# dtmf_v1.net
KiCad netlist of a schematic drawn in EAGLE
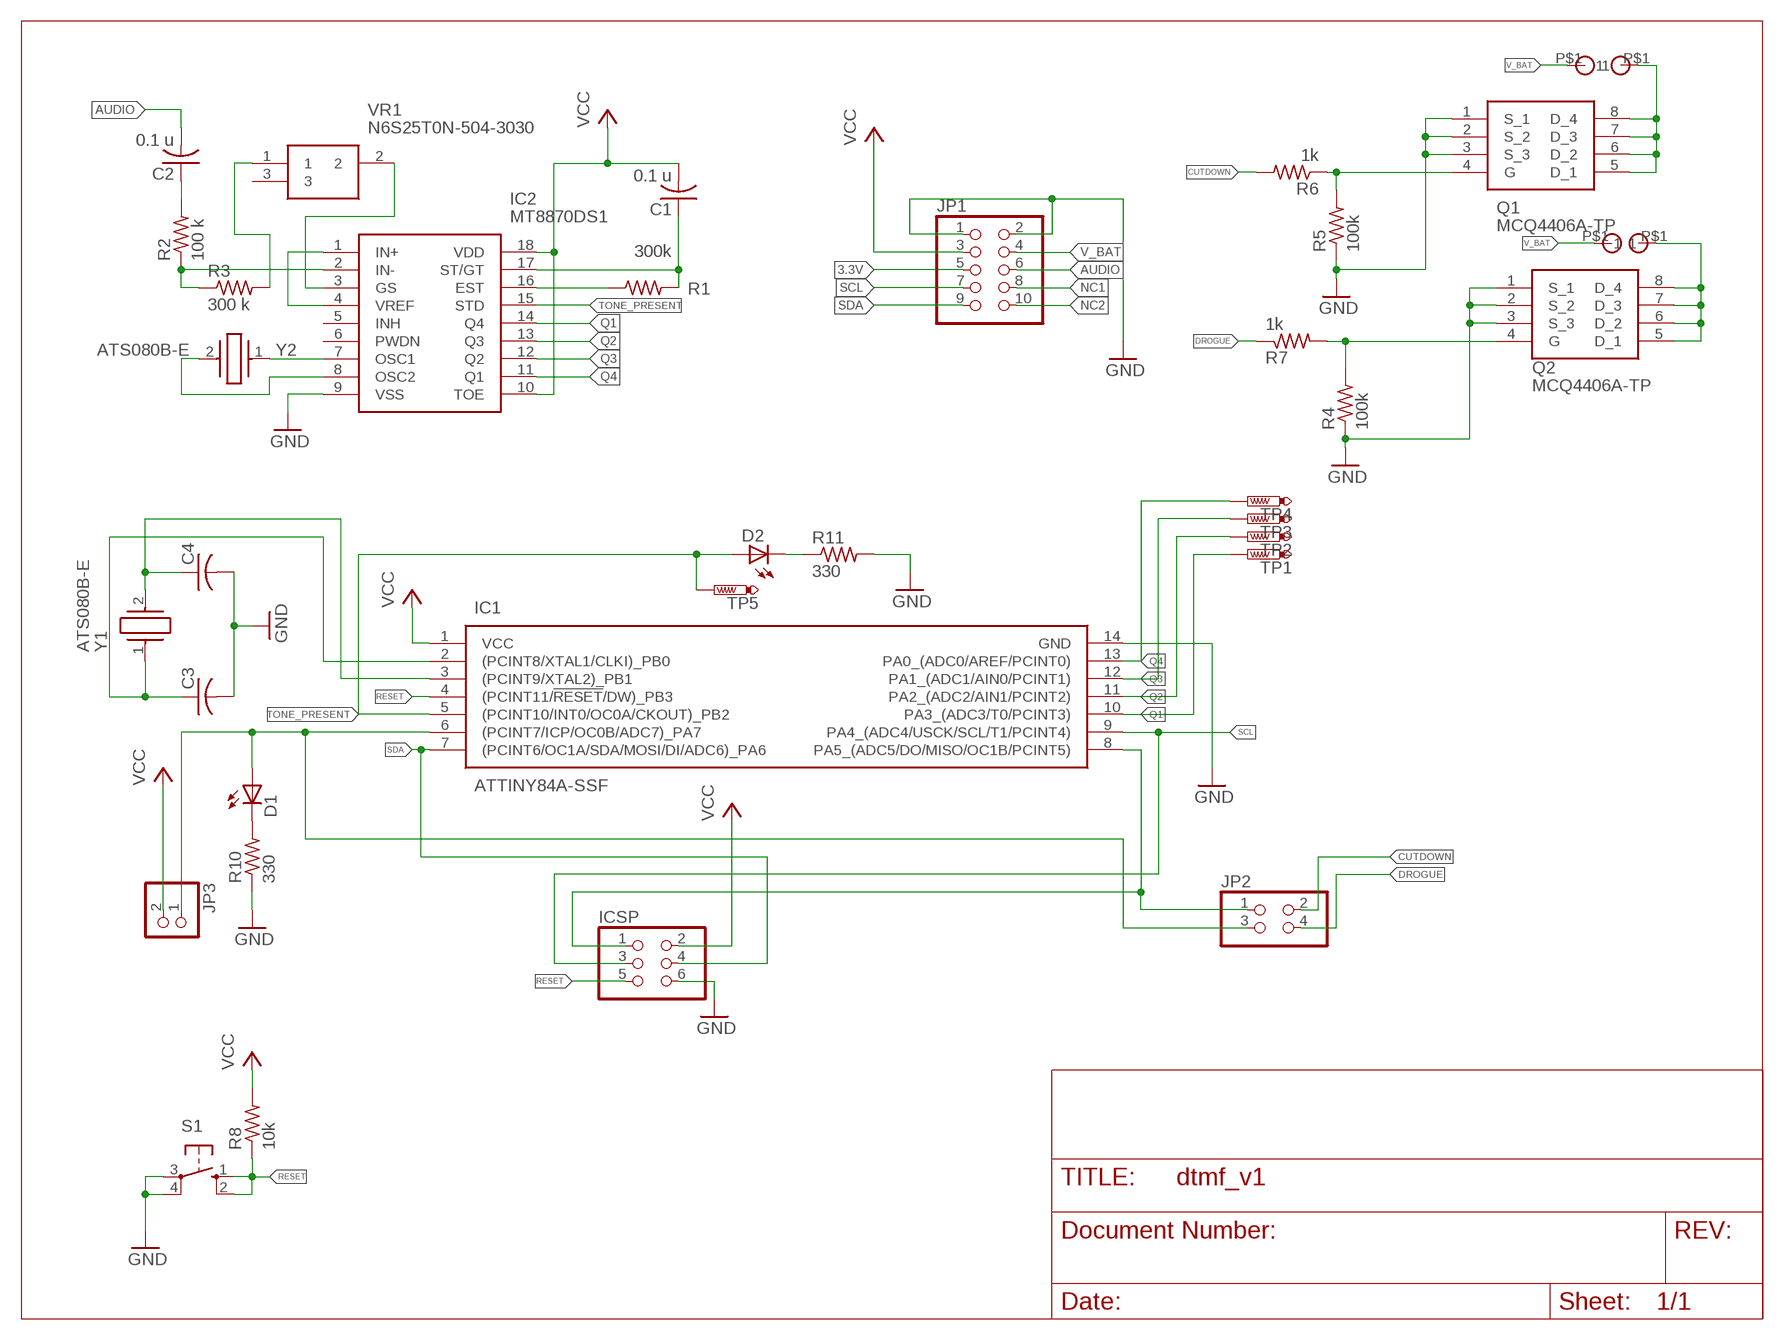
[diagram p0: schematic, sheet 1]

(export (version "E")
  (design (tool "Eeschema 10.0.6"))
  (components
    (comp (ref "C1")
      (value "0.1 u")
      (footprint "eagle-import:C0603")
      (libsource (lib "eagle-import") (part "C-USC0603"))
    )
    (comp (ref "C2")
      (value "0.1 u")
      (footprint "eagle-import:C0603")
      (libsource (lib "eagle-import") (part "C-USC0603"))
    )
    (comp (ref "C3")
      (value "C-USC0805")
      (footprint "eagle-import:C0805")
      (libsource (lib "eagle-import") (part "C-USC0805"))
    )
    (comp (ref "C4")
      (value "C-USC0805")
      (footprint "eagle-import:C0805")
      (libsource (lib "eagle-import") (part "C-USC0805"))
    )
    (comp (ref "D1")
      (value "LEDCHIP-LED0805")
      (footprint "eagle-import:CHIP-LED0805")
      (libsource (lib "eagle-import") (part "LEDCHIP-LED0805"))
    )
    (comp (ref "D2")
      (value "LEDCHIP-LED0805")
      (footprint "eagle-import:CHIP-LED0805")
      (libsource (lib "eagle-import") (part "LEDCHIP-LED0805"))
    )
    (comp (ref "IC1")
      (value "ATTINY84A-SSF")
      (footprint "eagle-import:SOIC127P600X175-14N")
      (fields (field (name "MOUSER_PART_NUMBER") "556-ATTINY84A-SSF"))
      (libsource (lib "eagle-import") (part "ATTINY84A-SSF"))
    )
    (comp (ref "IC2")
      (value "MT8870DS1")
      (footprint "eagle-import:SOIC127P1032X265-18N")
      (fields (field (name "MOUSER_PART_NUMBER") "494-MT8870DS1"))
      (libsource (lib "eagle-import") (part "MT8870DS1"))
    )
    (comp (ref "ICSP")
      (value "PINHD-2X3")
      (footprint "eagle-import:2X03")
      (libsource (lib "eagle-import") (part "PINHD-2X3"))
    )
    (comp (ref "JP1")
      (value "PINHD-2X5")
      (footprint "eagle-import:2X05")
      (libsource (lib "eagle-import") (part "PINHD-2X5"))
    )
    (comp (ref "JP2")
      (value "PINHD-2X2")
      (footprint "eagle-import:2X02")
      (libsource (lib "eagle-import") (part "PINHD-2X2"))
    )
    (comp (ref "JP3")
      (value "PINHD-1X2")
      (footprint "eagle-import:1X02")
      (libsource (lib "eagle-import") (part "PINHD-1X2"))
    )
    (comp (ref "Q1")
      (value "MCQ4406A-TP")
      (footprint "eagle-import:SOIC127P600X175-8N")
      (fields (field (name "MOUSER_PART_NUMBER") "833-MCQ4406A-TP"))
      (libsource (lib "eagle-import") (part "MCQ4406A-TP"))
    )
    (comp (ref "Q2")
      (value "MCQ4406A-TP")
      (footprint "eagle-import:SOIC127P600X175-8N")
      (fields (field (name "MOUSER_PART_NUMBER") "833-MCQ4406A-TP"))
      (libsource (lib "eagle-import") (part "MCQ4406A-TP"))
    )
    (comp (ref "R1")
      (value "300k")
      (footprint "eagle-import:M0805")
      (libsource (lib "eagle-import") (part "R-US_M0805"))
    )
    (comp (ref "R2")
      (value "100 k")
      (footprint "eagle-import:M0805")
      (libsource (lib "eagle-import") (part "R-US_M0805"))
    )
    (comp (ref "R3")
      (value "300 k")
      (footprint "eagle-import:M0805")
      (libsource (lib "eagle-import") (part "R-US_M0805"))
    )
    (comp (ref "R4")
      (value "100k")
      (footprint "eagle-import:M0805")
      (libsource (lib "eagle-import") (part "R-US_M0805"))
    )
    (comp (ref "R5")
      (value "100k")
      (footprint "eagle-import:M0805")
      (libsource (lib "eagle-import") (part "R-US_M0805"))
    )
    (comp (ref "R6")
      (value "1k")
      (footprint "eagle-import:M0805")
      (libsource (lib "eagle-import") (part "R-US_M0805"))
    )
    (comp (ref "R7")
      (value "1k")
      (footprint "eagle-import:M0805")
      (libsource (lib "eagle-import") (part "R-US_M0805"))
    )
    (comp (ref "R8")
      (value "10k")
      (footprint "eagle-import:0207_10")
      (libsource (lib "eagle-import") (part "R-US_0207/10"))
    )
    (comp (ref "R10")
      (value "330")
      (footprint "eagle-import:M0805")
      (libsource (lib "eagle-import") (part "R-US_M0805"))
    )
    (comp (ref "R11")
      (value "330")
      (footprint "eagle-import:M0805")
      (libsource (lib "eagle-import") (part "R-US_M0805"))
    )
    (comp (ref "S1")
      (value "10-XX")
      (footprint "eagle-import:B3F-10XX")
      (fields (field (name "MPN") "B3F-1000"))
      (libsource (lib "eagle-import") (part "10-XX"))
    )
    (comp (ref "TP1")
      (value "PTR1B1,27")
      (footprint "eagle-import:B1,27")
      (libsource (lib "eagle-import") (part "PTR1B1,27"))
    )
    (comp (ref "TP2")
      (value "PTR1B1,27")
      (footprint "eagle-import:B1,27")
      (libsource (lib "eagle-import") (part "PTR1B1,27"))
    )
    (comp (ref "TP3")
      (value "PTR1B1,27")
      (footprint "eagle-import:B1,27")
      (libsource (lib "eagle-import") (part "PTR1B1,27"))
    )
    (comp (ref "TP4")
      (value "PTR1B1,27")
      (footprint "eagle-import:B1,27")
      (libsource (lib "eagle-import") (part "PTR1B1,27"))
    )
    (comp (ref "TP5")
      (value "PTR1B1,27")
      (footprint "eagle-import:B1,27")
      (libsource (lib "eagle-import") (part "PTR1B1,27"))
    )
    (comp (ref "U$1")
      (value "M3_HOLE")
      (footprint "eagle-import:MOUNTING_PAD")
      (libsource (lib "eagle-import") (part "M3_HOLE"))
    )
    (comp (ref "U$2")
      (value "M3_HOLE")
      (footprint "eagle-import:MOUNTING_PAD")
      (libsource (lib "eagle-import") (part "M3_HOLE"))
    )
    (comp (ref "U$3")
      (value "M3_HOLE")
      (footprint "eagle-import:MOUNTING_PAD")
      (libsource (lib "eagle-import") (part "M3_HOLE"))
    )
    (comp (ref "U$4")
      (value "M3_HOLE")
      (footprint "eagle-import:MOUNTING_PAD")
      (libsource (lib "eagle-import") (part "M3_HOLE"))
    )
    (comp (ref "VR1")
      (value "N6S25T0N-504-3030")
      (footprint "eagle-import:N6S25T0N5043030")
      (fields (field (name "MOUSER_PART_NUMBER") "531-N6S25T0N5043030"))
      (libsource (lib "eagle-import") (part "N6S25T0N-504-3030"))
    )
    (comp (ref "Y1")
      (value "ATS080B-E")
      (footprint "eagle-import:ATS080BE")
      (fields (field (name "MOUSER_PART_NUMBER") "774-ATS080B-E"))
      (libsource (lib "eagle-import") (part "ATS080B-E"))
    )
    (comp (ref "Y2")
      (value "ATS080B-E")
      (footprint "eagle-import:ATS080BE")
      (fields (field (name "MOUSER_PART_NUMBER") "774-ATS080B-E"))
      (libsource (lib "eagle-import") (part "ATS080B-E"))
    )
  )
  (nets
    (net (code "1") (name "3.3V") (class "Default")
      (node (ref "JP1") (pin "5") (pinfunction "5_5") (pintype "passive"))
    )
    (net (code "2") (name "AUDIO") (class "Default")
      (node (ref "C2") (pin "2") (pinfunction "2_2") (pintype "passive"))
      (node (ref "JP1") (pin "6") (pinfunction "6_6") (pintype "passive"))
    )
    (net (code "3") (name "CUTDOWN") (class "Default")
      (node (ref "JP2") (pin "2") (pinfunction "2_2") (pintype "passive"))
      (node (ref "R6") (pin "2") (pinfunction "2_2") (pintype "passive"))
    )
    (net (code "4") (name "DROGUE") (class "Default")
      (node (ref "JP2") (pin "4") (pinfunction "4_4") (pintype "passive"))
      (node (ref "R7") (pin "1") (pinfunction "1_1") (pintype "passive"))
    )
    (net (code "5") (name "GND") (class "Default")
      (node (ref "C3") (pin "2") (pinfunction "2_2") (pintype "passive"))
      (node (ref "C4") (pin "2") (pinfunction "2_2") (pintype "passive"))
      (node (ref "IC1") (pin "14") (pinfunction "GND_14") (pintype "bidirectional"))
      (node (ref "IC2") (pin "9") (pinfunction "VSS_9") (pintype "bidirectional"))
      (node (ref "ICSP") (pin "6") (pinfunction "6_6") (pintype "passive"))
      (node (ref "JP1") (pin "1") (pinfunction "1_1") (pintype "passive"))
      (node (ref "JP1") (pin "2") (pinfunction "2_2") (pintype "passive"))
      (node (ref "Q1") (pin "1") (pinfunction "S_1_1") (pintype "bidirectional"))
      (node (ref "Q1") (pin "2") (pinfunction "S_2_2") (pintype "bidirectional"))
      (node (ref "Q1") (pin "3") (pinfunction "S_3_3") (pintype "bidirectional"))
      (node (ref "Q2") (pin "1") (pinfunction "S_1_1") (pintype "bidirectional"))
      (node (ref "Q2") (pin "2") (pinfunction "S_2_2") (pintype "bidirectional"))
      (node (ref "Q2") (pin "3") (pinfunction "S_3_3") (pintype "bidirectional"))
      (node (ref "R10") (pin "1") (pinfunction "1_1") (pintype "passive"))
      (node (ref "R11") (pin "2") (pinfunction "2_2") (pintype "passive"))
      (node (ref "R4") (pin "1") (pinfunction "1_1") (pintype "passive"))
      (node (ref "R5") (pin "1") (pinfunction "1_1") (pintype "passive"))
      (node (ref "S1") (pin "3") (pinfunction "P_3") (pintype "passive"))
      (node (ref "S1") (pin "4") (pinfunction "P1_4") (pintype "passive"))
    )
    (net (code "6") (name "NC1") (class "Default")
      (node (ref "JP1") (pin "8") (pinfunction "8_8") (pintype "passive"))
    )
    (net (code "7") (name "NC2") (class "Default")
      (node (ref "JP1") (pin "10") (pinfunction "10_10") (pintype "passive"))
    )
    (net (code "8") (name "Net-(C2-Pad1)") (class "Default")
      (node (ref "C2") (pin "1") (pinfunction "1_1") (pintype "passive"))
      (node (ref "R2") (pin "2") (pinfunction "2_2") (pintype "passive"))
    )
    (net (code "9") (name "Net-(D1-PadC)") (class "Default")
      (node (ref "D1") (pin "C") (pinfunction "C_C") (pintype "passive"))
      (node (ref "R10") (pin "2") (pinfunction "2_2") (pintype "passive"))
    )
    (net (code "10") (name "Net-(D2-PadC)") (class "Default")
      (node (ref "D2") (pin "C") (pinfunction "C_C") (pintype "passive"))
      (node (ref "R11") (pin "1") (pinfunction "1_1") (pintype "passive"))
    )
    (net (code "11") (name "Net-(IC1-(PCINT7{slash}ICP{slash}OC0B{slash}ADC7)_PA7)") (class "Default")
      (node (ref "D1") (pin "A") (pinfunction "A_A") (pintype "passive"))
      (node (ref "IC1") (pin "6") (pinfunction "(PCINT7/ICP/OC0B/ADC7)_PA7_6") (pintype "bidirectional"))
      (node (ref "JP2") (pin "3") (pinfunction "3_3") (pintype "passive"))
      (node (ref "JP3") (pin "1") (pinfunction "1_1") (pintype "passive"))
    )
    (net (code "12") (name "Net-(IC1-(PCINT8{slash}XTAL1{slash}CLKI)_PB0)") (class "Default")
      (node (ref "C3") (pin "1") (pinfunction "1_1") (pintype "passive"))
      (node (ref "IC1") (pin "2") (pinfunction "(PCINT8/XTAL1/CLKI)_PB0_2") (pintype "bidirectional"))
      (node (ref "Y1") (pin "1") (pinfunction "1_1") (pintype "bidirectional"))
    )
    (net (code "13") (name "Net-(IC1-(PCINT9{slash}XTAL2)_PB1)") (class "Default")
      (node (ref "C4") (pin "1") (pinfunction "1_1") (pintype "passive"))
      (node (ref "IC1") (pin "3") (pinfunction "(PCINT9/XTAL2)_PB1_3") (pintype "bidirectional"))
      (node (ref "Y1") (pin "2") (pinfunction "2_2") (pintype "bidirectional"))
    )
    (net (code "14") (name "Net-(IC1-PA5_(ADC5{slash}DO{slash}MISO{slash}OC1B{slash}PCINT5))") (class "Default")
      (node (ref "IC1") (pin "8") (pinfunction "PA5_(ADC5/DO/MISO/OC1B/PCINT5)_8") (pintype "bidirectional"))
      (node (ref "ICSP") (pin "1") (pinfunction "1_1") (pintype "passive"))
      (node (ref "JP2") (pin "1") (pinfunction "1_1") (pintype "passive"))
    )
    (net (code "15") (name "Net-(IC2-EST)") (class "Default")
      (node (ref "IC2") (pin "16") (pinfunction "EST_16") (pintype "bidirectional"))
      (node (ref "R1") (pin "1") (pinfunction "1_1") (pintype "passive"))
    )
    (net (code "16") (name "Net-(IC2-GS)") (class "Default")
      (node (ref "IC2") (pin "3") (pinfunction "GS_3") (pintype "bidirectional"))
      (node (ref "VR1") (pin "2") (pinfunction "2_2") (pintype "bidirectional"))
    )
    (net (code "17") (name "Net-(IC2-IN+)") (class "Default")
      (node (ref "IC2") (pin "1") (pinfunction "IN+_1") (pintype "bidirectional"))
      (node (ref "IC2") (pin "4") (pinfunction "VREF_4") (pintype "bidirectional"))
    )
    (net (code "18") (name "Net-(IC2-IN-)") (class "Default")
      (node (ref "IC2") (pin "2") (pinfunction "IN-_2") (pintype "bidirectional"))
      (node (ref "R2") (pin "1") (pinfunction "1_1") (pintype "passive"))
      (node (ref "R3") (pin "1") (pinfunction "1_1") (pintype "passive"))
    )
    (net (code "19") (name "Net-(IC2-OSC1)") (class "Default")
      (node (ref "IC2") (pin "7") (pinfunction "OSC1_7") (pintype "bidirectional"))
      (node (ref "Y2") (pin "1") (pinfunction "1_1") (pintype "bidirectional"))
    )
    (net (code "20") (name "Net-(IC2-OSC2)") (class "Default")
      (node (ref "IC2") (pin "8") (pinfunction "OSC2_8") (pintype "bidirectional"))
      (node (ref "Y2") (pin "2") (pinfunction "2_2") (pintype "bidirectional"))
    )
    (net (code "21") (name "Net-(IC2-ST{slash}GT)") (class "Default")
      (node (ref "C1") (pin "1") (pinfunction "1_1") (pintype "passive"))
      (node (ref "IC2") (pin "17") (pinfunction "ST/GT_17") (pintype "bidirectional"))
      (node (ref "R1") (pin "2") (pinfunction "2_2") (pintype "passive"))
    )
    (net (code "22") (name "Net-(Q1-D_1)") (class "Default")
      (node (ref "Q1") (pin "5") (pinfunction "D_1_5") (pintype "bidirectional"))
      (node (ref "Q1") (pin "6") (pinfunction "D_2_6") (pintype "bidirectional"))
      (node (ref "Q1") (pin "7") (pinfunction "D_3_7") (pintype "bidirectional"))
      (node (ref "Q1") (pin "8") (pinfunction "D_4_8") (pintype "bidirectional"))
      (node (ref "U$2") (pin "P$1") (pinfunction "1_P$1") (pintype "bidirectional"))
    )
    (net (code "23") (name "Net-(Q1-G)") (class "Default")
      (node (ref "Q1") (pin "4") (pinfunction "G_4") (pintype "bidirectional"))
      (node (ref "R5") (pin "2") (pinfunction "2_2") (pintype "passive"))
      (node (ref "R6") (pin "1") (pinfunction "1_1") (pintype "passive"))
    )
    (net (code "24") (name "Net-(Q2-D_1)") (class "Default")
      (node (ref "Q2") (pin "5") (pinfunction "D_1_5") (pintype "bidirectional"))
      (node (ref "Q2") (pin "6") (pinfunction "D_2_6") (pintype "bidirectional"))
      (node (ref "Q2") (pin "7") (pinfunction "D_3_7") (pintype "bidirectional"))
      (node (ref "Q2") (pin "8") (pinfunction "D_4_8") (pintype "bidirectional"))
      (node (ref "U$4") (pin "P$1") (pinfunction "1_P$1") (pintype "bidirectional"))
    )
    (net (code "25") (name "Net-(Q2-G)") (class "Default")
      (node (ref "Q2") (pin "4") (pinfunction "G_4") (pintype "bidirectional"))
      (node (ref "R4") (pin "2") (pinfunction "2_2") (pintype "passive"))
      (node (ref "R7") (pin "2") (pinfunction "2_2") (pintype "passive"))
    )
    (net (code "26") (name "Net-(R3-Pad2)") (class "Default")
      (node (ref "R3") (pin "2") (pinfunction "2_2") (pintype "passive"))
      (node (ref "VR1") (pin "1") (pinfunction "1_1") (pintype "bidirectional"))
    )
    (net (code "27") (name "Q1") (class "Default")
      (node (ref "IC1") (pin "10") (pinfunction "PA3_(ADC3/T0/PCINT3)_10") (pintype "bidirectional"))
      (node (ref "IC2") (pin "14") (pinfunction "Q4_14") (pintype "bidirectional"))
      (node (ref "TP1") (pin "TP") (pinfunction "TP_TP") (pintype "input"))
    )
    (net (code "28") (name "Q2") (class "Default")
      (node (ref "IC1") (pin "11") (pinfunction "PA2_(ADC2/AIN1/PCINT2)_11") (pintype "bidirectional"))
      (node (ref "IC2") (pin "13") (pinfunction "Q3_13") (pintype "bidirectional"))
      (node (ref "TP2") (pin "TP") (pinfunction "TP_TP") (pintype "input"))
    )
    (net (code "29") (name "Q3") (class "Default")
      (node (ref "IC1") (pin "12") (pinfunction "PA1_(ADC1/AIN0/PCINT1)_12") (pintype "bidirectional"))
      (node (ref "IC2") (pin "12") (pinfunction "Q2_12") (pintype "bidirectional"))
      (node (ref "TP3") (pin "TP") (pinfunction "TP_TP") (pintype "input"))
    )
    (net (code "30") (name "Q4") (class "Default")
      (node (ref "IC1") (pin "13") (pinfunction "PA0_(ADC0/AREF/PCINT0)_13") (pintype "bidirectional"))
      (node (ref "IC2") (pin "11") (pinfunction "Q1_11") (pintype "bidirectional"))
      (node (ref "TP4") (pin "TP") (pinfunction "TP_TP") (pintype "input"))
    )
    (net (code "31") (name "RESET") (class "Default")
      (node (ref "IC1") (pin "4") (pinfunction "(PCINT11/~{RESET}/DW)_PB3_4") (pintype "bidirectional"))
      (node (ref "ICSP") (pin "5") (pinfunction "5_5") (pintype "passive"))
      (node (ref "R8") (pin "1") (pinfunction "1_1") (pintype "passive"))
      (node (ref "S1") (pin "1") (pinfunction "S_1") (pintype "passive"))
      (node (ref "S1") (pin "2") (pinfunction "S1_2") (pintype "passive"))
    )
    (net (code "32") (name "SCL") (class "Default")
      (node (ref "IC1") (pin "9") (pinfunction "PA4_(ADC4/USCK/SCL/T1/PCINT4)_9") (pintype "bidirectional"))
      (node (ref "ICSP") (pin "3") (pinfunction "3_3") (pintype "passive"))
      (node (ref "JP1") (pin "7") (pinfunction "7_7") (pintype "passive"))
    )
    (net (code "33") (name "SDA") (class "Default")
      (node (ref "IC1") (pin "7") (pinfunction "(PCINT6/OC1A/SDA/MOSI/DI/ADC6)_PA6_7") (pintype "bidirectional"))
      (node (ref "ICSP") (pin "4") (pinfunction "4_4") (pintype "passive"))
      (node (ref "JP1") (pin "9") (pinfunction "9_9") (pintype "passive"))
    )
    (net (code "34") (name "TONE_PRESENT") (class "Default")
      (node (ref "D2") (pin "A") (pinfunction "A_A") (pintype "passive"))
      (node (ref "IC1") (pin "5") (pinfunction "(PCINT10/INT0/OC0A/CKOUT)_PB2_5") (pintype "bidirectional"))
      (node (ref "IC2") (pin "15") (pinfunction "STD_15") (pintype "bidirectional"))
      (node (ref "TP5") (pin "TP") (pinfunction "TP_TP") (pintype "input"))
    )
    (net (code "35") (name "VCC") (class "Default")
      (node (ref "C1") (pin "2") (pinfunction "2_2") (pintype "passive"))
      (node (ref "IC1") (pin "1") (pinfunction "VCC_1") (pintype "bidirectional"))
      (node (ref "IC2") (pin "10") (pinfunction "TOE_10") (pintype "bidirectional"))
      (node (ref "IC2") (pin "18") (pinfunction "VDD_18") (pintype "bidirectional"))
      (node (ref "ICSP") (pin "2") (pinfunction "2_2") (pintype "passive"))
      (node (ref "JP1") (pin "3") (pinfunction "3_3") (pintype "passive"))
      (node (ref "JP3") (pin "2") (pinfunction "2_2") (pintype "passive"))
      (node (ref "R8") (pin "2") (pinfunction "2_2") (pintype "passive"))
    )
    (net (code "36") (name "V_BAT") (class "Default")
      (node (ref "JP1") (pin "4") (pinfunction "4_4") (pintype "passive"))
      (node (ref "U$1") (pin "P$1") (pinfunction "1_P$1") (pintype "bidirectional"))
      (node (ref "U$3") (pin "P$1") (pinfunction "1_P$1") (pintype "bidirectional"))
    )
    (net (code "37") (name "unconnected-(IC2-INH-Pad5)") (class "Default")
      (node (ref "IC2") (pin "5") (pinfunction "INH_5") (pintype "bidirectional"))
    )
    (net (code "38") (name "unconnected-(IC2-PWDN-Pad6)") (class "Default")
      (node (ref "IC2") (pin "6") (pinfunction "PWDN_6") (pintype "bidirectional"))
    )
    (net (code "39") (name "unconnected-(VR1-Pad3)") (class "Default")
      (node (ref "VR1") (pin "3") (pinfunction "3_3") (pintype "bidirectional"))
    )
  )
)
